# OLM-jee-ircam.net
KiCad netlist of a schematic drawn in EAGLE
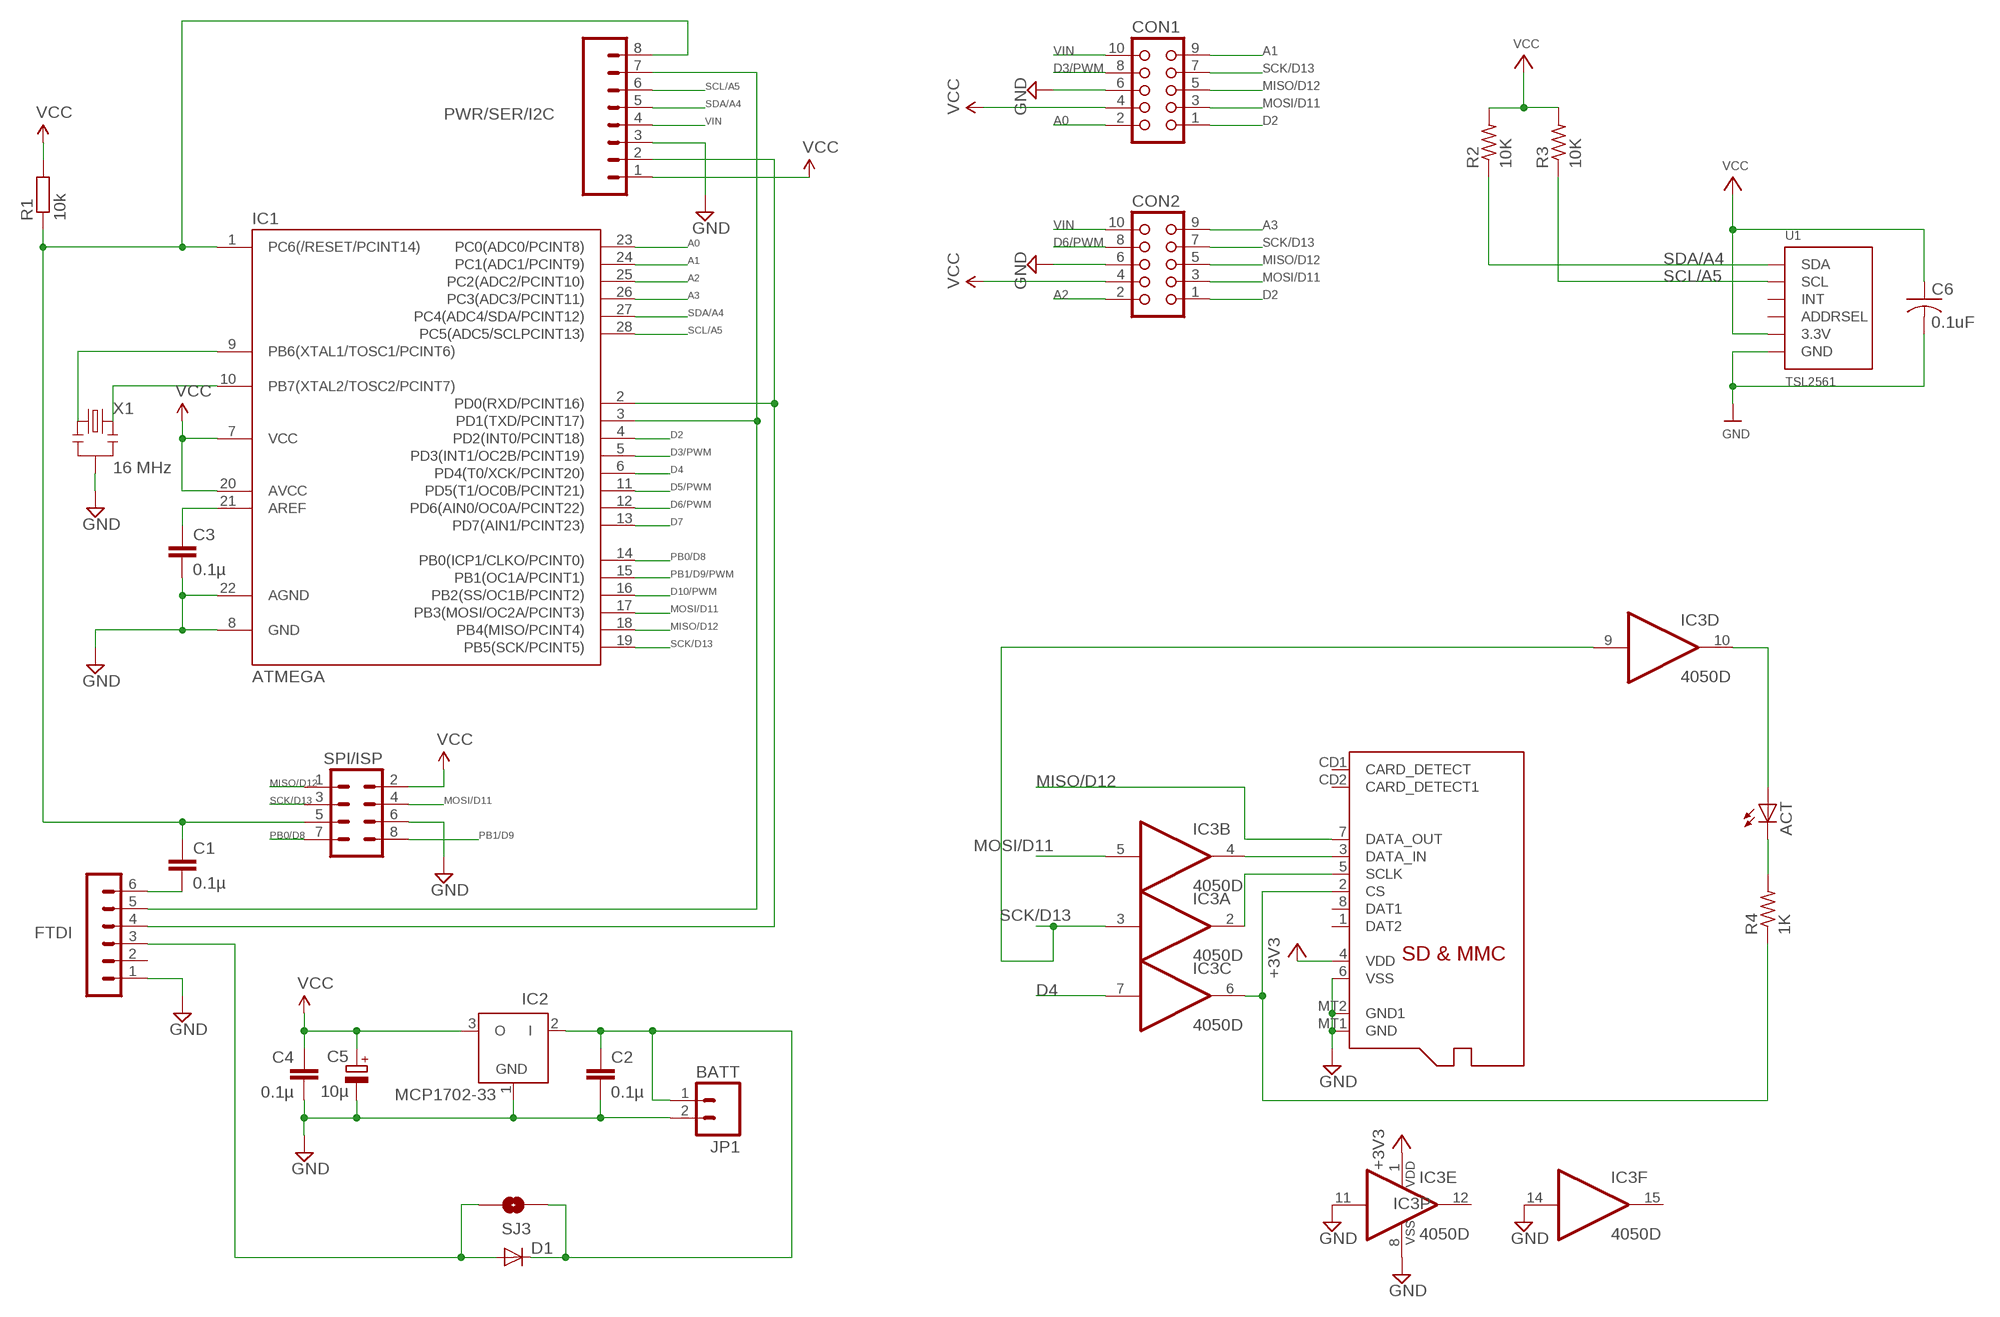
[diagram p0: schematic, sheet 1]

(export (version "E")
  (design (tool "Eeschema 10.0.6"))
  (components
    (comp (ref "ACT")
      (value "LEDCHIP-LED0805")
      (footprint "eagle-import:CHIP-LED0805")
      (libsource (lib "eagle-import") (part "LEDCHIP-LED0805"))
    )
    (comp (ref "C1")
      (value "0.1µ")
      (footprint "eagle-import:C025-024X044")
      (libsource (lib "eagle-import") (part "C-EU025-024X044"))
    )
    (comp (ref "C2")
      (value "0.1µ")
      (footprint "eagle-import:C025-024X044")
      (libsource (lib "eagle-import") (part "C-EU025-024X044"))
    )
    (comp (ref "C3")
      (value "0.1µ")
      (footprint "eagle-import:C025-024X044")
      (libsource (lib "eagle-import") (part "C-EU025-024X044"))
    )
    (comp (ref "C4")
      (value "0.1µ")
      (footprint "eagle-import:C025-024X044")
      (libsource (lib "eagle-import") (part "C-EU025-024X044"))
    )
    (comp (ref "C5")
      (value "10µ")
      (footprint "eagle-import:E1,8-4")
      (libsource (lib "eagle-import") (part "CPOL-EUE1.8-4"))
    )
    (comp (ref "C6")
      (value "0.1uF")
      (footprint "eagle-import:C0805")
      (libsource (lib "eagle-import") (part "C-USC0805"))
    )
    (comp (ref "CON1")
      (value "CON10L")
      (footprint "eagle-import:CON10L")
      (libsource (lib "eagle-import") (part "CON10L"))
    )
    (comp (ref "CON2")
      (value "CON10L")
      (footprint "eagle-import:CON10L")
      (libsource (lib "eagle-import") (part "CON10L"))
    )
    (comp (ref "D1")
      (value "DIODE-D-5")
      (footprint "eagle-import:D-5")
      (libsource (lib "eagle-import") (part "DIODE-D-5"))
    )
    (comp (ref "FTDI")
      (value "FTDI")
      (footprint "eagle-import:MA06-1")
      (libsource (lib "eagle-import") (part "MA06-1"))
    )
    (comp (ref "IC1")
      (value "ATMEGA")
      (footprint "eagle-import:DIL28-3")
      (libsource (lib "eagle-import") (part "ATMEGA48/88/168-PU"))
    )
    (comp (ref "IC2")
      (value "MCP1702-33")
      (footprint "eagle-import:TO92")
      (libsource (lib "eagle-import") (part "MCP1702Z"))
    )
    (comp (ref "IC3")
      (value "4050D")
      (footprint "eagle-import:SO16")
      (libsource (lib "eagle-import") (part "4050D"))
    )
    (comp (ref "JP1")
      (value "BATT")
      (footprint "eagle-import:1X02_LOCK_LONGPADS")
      (libsource (lib "eagle-import") (part "M02LOCK_LONGPADS"))
    )
    (comp (ref "PWR/SER/I2C")
      (value "M08")
      (footprint "eagle-import:1X08")
      (libsource (lib "eagle-import") (part "M08"))
    )
    (comp (ref "R1")
      (value "10k")
      (footprint "eagle-import:0204_7")
      (libsource (lib "eagle-import") (part "R-EU_0204/7"))
    )
    (comp (ref "R2")
      (value "10K")
      (footprint "eagle-import:R0805")
      (libsource (lib "eagle-import") (part "R-US_R0805"))
    )
    (comp (ref "R3")
      (value "10K")
      (footprint "eagle-import:R0805")
      (libsource (lib "eagle-import") (part "R-US_R0805"))
    )
    (comp (ref "R4")
      (value "1K")
      (footprint "eagle-import:R0805")
      (libsource (lib "eagle-import") (part "R-US_R0805"))
    )
    (comp (ref "SJ3")
      (value "SOLDERJUMPERTRACE")
      (footprint "eagle-import:SJ_2S-TRACE")
      (libsource (lib "eagle-import") (part "SOLDERJUMPERTRACE"))
    )
    (comp (ref "SV7")
      (value "SPI/ISP")
      (footprint "eagle-import:MA04-2")
      (libsource (lib "eagle-import") (part "MA04-2"))
    )
    (comp (ref "U1")
      (value "TSL2561")
      (footprint "eagle-import:TSL2561_FN")
      (libsource (lib "eagle-import") (part "TSL2561"))
    )
    (comp (ref "X1")
      (value "16 MHz")
      (footprint "eagle-import:RESONATOR-PTH")
      (libsource (lib "eagle-import") (part "RESONATORPTH"))
    )
    (comp (ref "X2")
      (value "MICROSD")
      (footprint "eagle-import:MICROSD")
      (libsource (lib "eagle-import") (part "MICROSD"))
    )
  )
  (nets
    (net (code "1") (name "+3V3") (class "Default")
      (node (ref "IC3") (pin "1") (pinfunction "VDD_1") (pintype "power_in"))
      (node (ref "X2") (pin "4") (pinfunction "VDD_4") (pintype "power_in"))
    )
    (net (code "2") (name "/A0") (class "Default")
      (node (ref "CON1") (pin "2") (pinfunction "2_2") (pintype "passive"))
      (node (ref "IC1") (pin "23") (pinfunction "PC0(ADC0/PCINT8)_23") (pintype "bidirectional"))
    )
    (net (code "3") (name "/A1") (class "Default")
      (node (ref "CON1") (pin "9") (pinfunction "9_9") (pintype "passive"))
      (node (ref "IC1") (pin "24") (pinfunction "PC1(ADC1/PCINT9)_24") (pintype "bidirectional"))
    )
    (net (code "4") (name "/A2") (class "Default")
      (node (ref "CON2") (pin "2") (pinfunction "2_2") (pintype "passive"))
      (node (ref "IC1") (pin "25") (pinfunction "PC2(ADC2/PCINT10)_25") (pintype "bidirectional"))
    )
    (net (code "5") (name "/A3") (class "Default")
      (node (ref "CON2") (pin "9") (pinfunction "9_9") (pintype "passive"))
      (node (ref "IC1") (pin "26") (pinfunction "PC3(ADC3/PCINT11)_26") (pintype "bidirectional"))
    )
    (net (code "6") (name "/D2") (class "Default")
      (node (ref "CON1") (pin "1") (pinfunction "1_1") (pintype "passive"))
      (node (ref "CON2") (pin "1") (pinfunction "1_1") (pintype "passive"))
      (node (ref "IC1") (pin "4") (pinfunction "PD2(INT0/PCINT18)_4") (pintype "bidirectional"))
    )
    (net (code "7") (name "/D3{slash}PWM") (class "Default")
      (node (ref "CON1") (pin "8") (pinfunction "8_8") (pintype "passive"))
      (node (ref "IC1") (pin "5") (pinfunction "PD3(INT1/OC2B/PCINT19)_5") (pintype "bidirectional"))
    )
    (net (code "8") (name "/D4") (class "Default")
      (node (ref "IC1") (pin "6") (pinfunction "PD4(T0/XCK/PCINT20)_6") (pintype "bidirectional"))
      (node (ref "IC3") (pin "7") (pinfunction "I_7") (pintype "input"))
    )
    (net (code "9") (name "/D5{slash}PWM") (class "Default")
      (node (ref "IC1") (pin "11") (pinfunction "PD5(T1/OC0B/PCINT21)_11") (pintype "bidirectional"))
    )
    (net (code "10") (name "/D6{slash}PWM") (class "Default")
      (node (ref "CON2") (pin "8") (pinfunction "8_8") (pintype "passive"))
      (node (ref "IC1") (pin "12") (pinfunction "PD6(AIN0/OC0A/PCINT22)_12") (pintype "bidirectional"))
    )
    (net (code "11") (name "/D7") (class "Default")
      (node (ref "IC1") (pin "13") (pinfunction "PD7(AIN1/PCINT23)_13") (pintype "bidirectional"))
    )
    (net (code "12") (name "/D10{slash}PWM") (class "Default")
      (node (ref "IC1") (pin "16") (pinfunction "PB2(SS/OC1B/PCINT2)_16") (pintype "bidirectional"))
    )
    (net (code "13") (name "/MISO{slash}D12") (class "Default")
      (node (ref "CON1") (pin "5") (pinfunction "5_5") (pintype "passive"))
      (node (ref "CON2") (pin "5") (pinfunction "5_5") (pintype "passive"))
      (node (ref "IC1") (pin "18") (pinfunction "PB4(MISO/PCINT4)_18") (pintype "bidirectional"))
      (node (ref "SV7") (pin "1") (pinfunction "1_1") (pintype "passive"))
      (node (ref "X2") (pin "7") (pinfunction "DATA_OUT_7") (pintype "output"))
    )
    (net (code "14") (name "/MOSI{slash}D11") (class "Default")
      (node (ref "CON1") (pin "3") (pinfunction "3_3") (pintype "passive"))
      (node (ref "CON2") (pin "3") (pinfunction "3_3") (pintype "passive"))
      (node (ref "IC1") (pin "17") (pinfunction "PB3(MOSI/OC2A/PCINT3)_17") (pintype "bidirectional"))
      (node (ref "IC3") (pin "5") (pinfunction "I_5") (pintype "input"))
      (node (ref "SV7") (pin "4") (pinfunction "4_4") (pintype "passive"))
    )
    (net (code "15") (name "/PB0{slash}D8") (class "Default")
      (node (ref "IC1") (pin "14") (pinfunction "PB0(ICP1/CLKO/PCINT0)_14") (pintype "bidirectional"))
      (node (ref "SV7") (pin "7") (pinfunction "7_7") (pintype "passive"))
    )
    (net (code "16") (name "/PB1{slash}D9") (class "Default")
      (node (ref "SV7") (pin "8") (pinfunction "8_8") (pintype "passive"))
    )
    (net (code "17") (name "/PB1{slash}D9{slash}PWM") (class "Default")
      (node (ref "IC1") (pin "15") (pinfunction "PB1(OC1A/PCINT1)_15") (pintype "bidirectional"))
    )
    (net (code "18") (name "/SCK{slash}D13") (class "Default")
      (node (ref "CON1") (pin "7") (pinfunction "7_7") (pintype "passive"))
      (node (ref "CON2") (pin "7") (pinfunction "7_7") (pintype "passive"))
      (node (ref "IC1") (pin "19") (pinfunction "PB5(SCK/PCINT5)_19") (pintype "bidirectional"))
      (node (ref "IC3") (pin "3") (pinfunction "I_3") (pintype "input"))
      (node (ref "IC3") (pin "9") (pinfunction "I_9") (pintype "input"))
      (node (ref "SV7") (pin "3") (pinfunction "3_3") (pintype "passive"))
    )
    (net (code "19") (name "/SCL{slash}A5") (class "Default")
      (node (ref "IC1") (pin "28") (pinfunction "PC5(ADC5/SCLPCINT13)_28") (pintype "bidirectional"))
      (node (ref "PWR/SER/I2C") (pin "6") (pinfunction "6_6") (pintype "passive"))
      (node (ref "R3") (pin "1") (pinfunction "1_1") (pintype "passive"))
      (node (ref "U1") (pin "CLK") (pinfunction "SCL_CLK") (pintype "bidirectional"))
    )
    (net (code "20") (name "/SDA{slash}A4") (class "Default")
      (node (ref "IC1") (pin "27") (pinfunction "PC4(ADC4/SDA/PCINT12)_27") (pintype "bidirectional"))
      (node (ref "PWR/SER/I2C") (pin "5") (pinfunction "5_5") (pintype "passive"))
      (node (ref "R2") (pin "1") (pinfunction "1_1") (pintype "passive"))
      (node (ref "U1") (pin "DATA") (pinfunction "SDA_DATA") (pintype "bidirectional"))
    )
    (net (code "21") (name "/VIN") (class "Default")
      (node (ref "CON1") (pin "10") (pinfunction "10_10") (pintype "passive"))
      (node (ref "CON2") (pin "10") (pinfunction "10_10") (pintype "passive"))
      (node (ref "PWR/SER/I2C") (pin "4") (pinfunction "4_4") (pintype "passive"))
    )
    (net (code "22") (name "GND") (class "Default")
      (node (ref "C2") (pin "2") (pinfunction "2_2") (pintype "passive"))
      (node (ref "C3") (pin "2") (pinfunction "2_2") (pintype "passive"))
      (node (ref "C4") (pin "2") (pinfunction "2_2") (pintype "passive"))
      (node (ref "C5") (pin "-") (pinfunction "-_-") (pintype "passive"))
      (node (ref "C6") (pin "2") (pinfunction "2_2") (pintype "passive"))
      (node (ref "CON1") (pin "6") (pinfunction "6_6") (pintype "passive"))
      (node (ref "CON2") (pin "6") (pinfunction "6_6") (pintype "passive"))
      (node (ref "FTDI") (pin "1") (pinfunction "1_1") (pintype "passive"))
      (node (ref "IC1") (pin "22") (pinfunction "AGND_22") (pintype "power_in"))
      (node (ref "IC1") (pin "8") (pinfunction "GND_8") (pintype "power_in"))
      (node (ref "IC2") (pin "1") (pinfunction "GND_1") (pintype "power_in"))
      (node (ref "IC3") (pin "11") (pinfunction "I_11") (pintype "input"))
      (node (ref "IC3") (pin "14") (pinfunction "I_14") (pintype "input"))
      (node (ref "IC3") (pin "8") (pinfunction "VSS_8") (pintype "power_in"))
      (node (ref "JP1") (pin "2") (pinfunction "2_2") (pintype "passive"))
      (node (ref "PWR/SER/I2C") (pin "3") (pinfunction "3_3") (pintype "passive"))
      (node (ref "SV7") (pin "6") (pinfunction "6_6") (pintype "passive"))
      (node (ref "U1") (pin "VSS") (pinfunction "GND_VSS") (pintype "bidirectional"))
      (node (ref "X1") (pin "2") (pinfunction "2_2") (pintype "passive"))
      (node (ref "X2") (pin "6") (pinfunction "VSS_6") (pintype "power_in"))
      (node (ref "X2") (pin "MT1") (pinfunction "GND_MT1") (pintype "power_in"))
      (node (ref "X2") (pin "MT2") (pinfunction "GND1_MT2") (pintype "power_in"))
    )
    (net (code "23") (name "Net-(ACT-PadC)") (class "Default")
      (node (ref "ACT") (pin "C") (pinfunction "C_C") (pintype "passive"))
      (node (ref "R4") (pin "2") (pinfunction "2_2") (pintype "passive"))
    )
    (net (code "24") (name "Net-(C1-Pad2)") (class "Default")
      (node (ref "C1") (pin "2") (pinfunction "2_2") (pintype "passive"))
      (node (ref "FTDI") (pin "6") (pinfunction "6_6") (pintype "passive"))
    )
    (net (code "25") (name "Net-(D1-PadA)") (class "Default")
      (node (ref "D1") (pin "A") (pinfunction "A_A") (pintype "passive"))
      (node (ref "FTDI") (pin "3") (pinfunction "3_3") (pintype "passive"))
      (node (ref "SJ3") (pin "2") (pinfunction "2_2") (pintype "passive"))
    )
    (net (code "26") (name "Net-(IC1-AREF)") (class "Default")
      (node (ref "C3") (pin "1") (pinfunction "1_1") (pintype "passive"))
      (node (ref "IC1") (pin "21") (pinfunction "AREF_21") (pintype "passive"))
    )
    (net (code "27") (name "Net-(IC1-PB6(XTAL1{slash}TOSC1{slash}PCINT6))") (class "Default")
      (node (ref "IC1") (pin "9") (pinfunction "PB6(XTAL1/TOSC1/PCINT6)_9") (pintype "bidirectional"))
      (node (ref "X1") (pin "1") (pinfunction "1_1") (pintype "passive"))
    )
    (net (code "28") (name "Net-(IC1-PB7(XTAL2{slash}TOSC2{slash}PCINT7))") (class "Default")
      (node (ref "IC1") (pin "10") (pinfunction "PB7(XTAL2/TOSC2/PCINT7)_10") (pintype "bidirectional"))
      (node (ref "X1") (pin "3") (pinfunction "3_3") (pintype "passive"))
    )
    (net (code "29") (name "Net-(IC1-PC6({slash}RESET{slash}PCINT14))") (class "Default")
      (node (ref "C1") (pin "1") (pinfunction "1_1") (pintype "passive"))
      (node (ref "IC1") (pin "1") (pinfunction "PC6(/RESET/PCINT14)_1") (pintype "bidirectional"))
      (node (ref "PWR/SER/I2C") (pin "8") (pinfunction "8_8") (pintype "passive"))
      (node (ref "R1") (pin "1") (pinfunction "1_1") (pintype "passive"))
      (node (ref "SV7") (pin "5") (pinfunction "5_5") (pintype "passive"))
    )
    (net (code "30") (name "Net-(IC1-PD0(RXD{slash}PCINT16))") (class "Default")
      (node (ref "FTDI") (pin "4") (pinfunction "4_4") (pintype "passive"))
      (node (ref "IC1") (pin "2") (pinfunction "PD0(RXD/PCINT16)_2") (pintype "bidirectional"))
      (node (ref "PWR/SER/I2C") (pin "2") (pinfunction "2_2") (pintype "passive"))
    )
    (net (code "31") (name "Net-(IC1-PD1(TXD{slash}PCINT17))") (class "Default")
      (node (ref "FTDI") (pin "5") (pinfunction "5_5") (pintype "passive"))
      (node (ref "IC1") (pin "3") (pinfunction "PD1(TXD/PCINT17)_3") (pintype "bidirectional"))
      (node (ref "PWR/SER/I2C") (pin "7") (pinfunction "7_7") (pintype "passive"))
    )
    (net (code "32") (name "Net-(IC2-I)") (class "Default")
      (node (ref "C2") (pin "1") (pinfunction "1_1") (pintype "passive"))
      (node (ref "D1") (pin "C") (pinfunction "C_C") (pintype "passive"))
      (node (ref "IC2") (pin "2") (pinfunction "I_2") (pintype "input"))
      (node (ref "JP1") (pin "1") (pinfunction "1_1") (pintype "passive"))
      (node (ref "SJ3") (pin "1") (pinfunction "1_1") (pintype "passive"))
    )
    (net (code "33") (name "Net-(IC3A-O)") (class "Default")
      (node (ref "IC3") (pin "2") (pinfunction "O_2") (pintype "output"))
      (node (ref "X2") (pin "5") (pinfunction "SCLK_5") (pintype "input"))
    )
    (net (code "34") (name "Net-(IC3B-O)") (class "Default")
      (node (ref "IC3") (pin "4") (pinfunction "O_4") (pintype "output"))
      (node (ref "X2") (pin "3") (pinfunction "DATA_IN_3") (pintype "input"))
    )
    (net (code "35") (name "Net-(IC3C-O)") (class "Default")
      (node (ref "IC3") (pin "6") (pinfunction "O_6") (pintype "output"))
      (node (ref "R4") (pin "1") (pinfunction "1_1") (pintype "passive"))
      (node (ref "X2") (pin "2") (pinfunction "CS_2") (pintype "input"))
    )
    (net (code "36") (name "Net-(IC3D-O)") (class "Default")
      (node (ref "ACT") (pin "A") (pinfunction "A_A") (pintype "passive"))
      (node (ref "IC3") (pin "10") (pinfunction "O_10") (pintype "output"))
    )
    (net (code "37") (name "VCC") (class "Default")
      (node (ref "C4") (pin "1") (pinfunction "1_1") (pintype "passive"))
      (node (ref "C5") (pin "+") (pinfunction "+_+") (pintype "passive"))
      (node (ref "C6") (pin "1") (pinfunction "1_1") (pintype "passive"))
      (node (ref "CON1") (pin "4") (pinfunction "4_4") (pintype "passive"))
      (node (ref "CON2") (pin "4") (pinfunction "4_4") (pintype "passive"))
      (node (ref "IC1") (pin "20") (pinfunction "AVCC_20") (pintype "passive"))
      (node (ref "IC1") (pin "7") (pinfunction "VCC_7") (pintype "power_in"))
      (node (ref "IC2") (pin "3") (pinfunction "O_3") (pintype "input"))
      (node (ref "PWR/SER/I2C") (pin "1") (pinfunction "1_1") (pintype "passive"))
      (node (ref "R1") (pin "2") (pinfunction "2_2") (pintype "passive"))
      (node (ref "R2") (pin "2") (pinfunction "2_2") (pintype "passive"))
      (node (ref "R3") (pin "2") (pinfunction "2_2") (pintype "passive"))
      (node (ref "SV7") (pin "2") (pinfunction "2_2") (pintype "passive"))
      (node (ref "U1") (pin "VDD") (pinfunction "3.3V_VDD") (pintype "bidirectional"))
    )
    (net (code "38") (name "unconnected-(FTDI-Pad2)") (class "Default")
      (node (ref "FTDI") (pin "2") (pinfunction "2_2") (pintype "passive"))
    )
    (net (code "39") (name "unconnected-(IC3E-O-Pad12)") (class "Default")
      (node (ref "IC3") (pin "12") (pinfunction "O_12") (pintype "output"))
    )
    (net (code "40") (name "unconnected-(IC3F-O-Pad15)") (class "Default")
      (node (ref "IC3") (pin "15") (pinfunction "O_15") (pintype "output"))
    )
    (net (code "41") (name "unconnected-(U1-ADDRSEL-PadADR)") (class "Default")
      (node (ref "U1") (pin "ADR") (pinfunction "ADDRSEL_ADR") (pintype "bidirectional"))
    )
    (net (code "42") (name "unconnected-(U1-PadINT)") (class "Default")
      (node (ref "U1") (pin "INT") (pinfunction "INT_INT") (pintype "bidirectional"))
    )
    (net (code "43") (name "unconnected-(X2-CARD_DETECT-PadCD1)") (class "Default")
      (node (ref "X2") (pin "CD1") (pinfunction "CARD_DETECT_CD1") (pintype "passive"))
    )
    (net (code "44") (name "unconnected-(X2-CARD_DETECT1-PadCD2)") (class "Default")
      (node (ref "X2") (pin "CD2") (pinfunction "CARD_DETECT1_CD2") (pintype "passive"))
    )
    (net (code "45") (name "unconnected-(X2-DAT1-Pad8)") (class "Default")
      (node (ref "X2") (pin "8") (pinfunction "DAT1_8") (pintype "bidirectional"))
    )
    (net (code "46") (name "unconnected-(X2-DAT2-Pad1)") (class "Default")
      (node (ref "X2") (pin "1") (pinfunction "DAT2_1") (pintype "bidirectional"))
    )
  )
)
